# axxl_v0_1.net
KiCad netlist of a schematic drawn in EAGLE
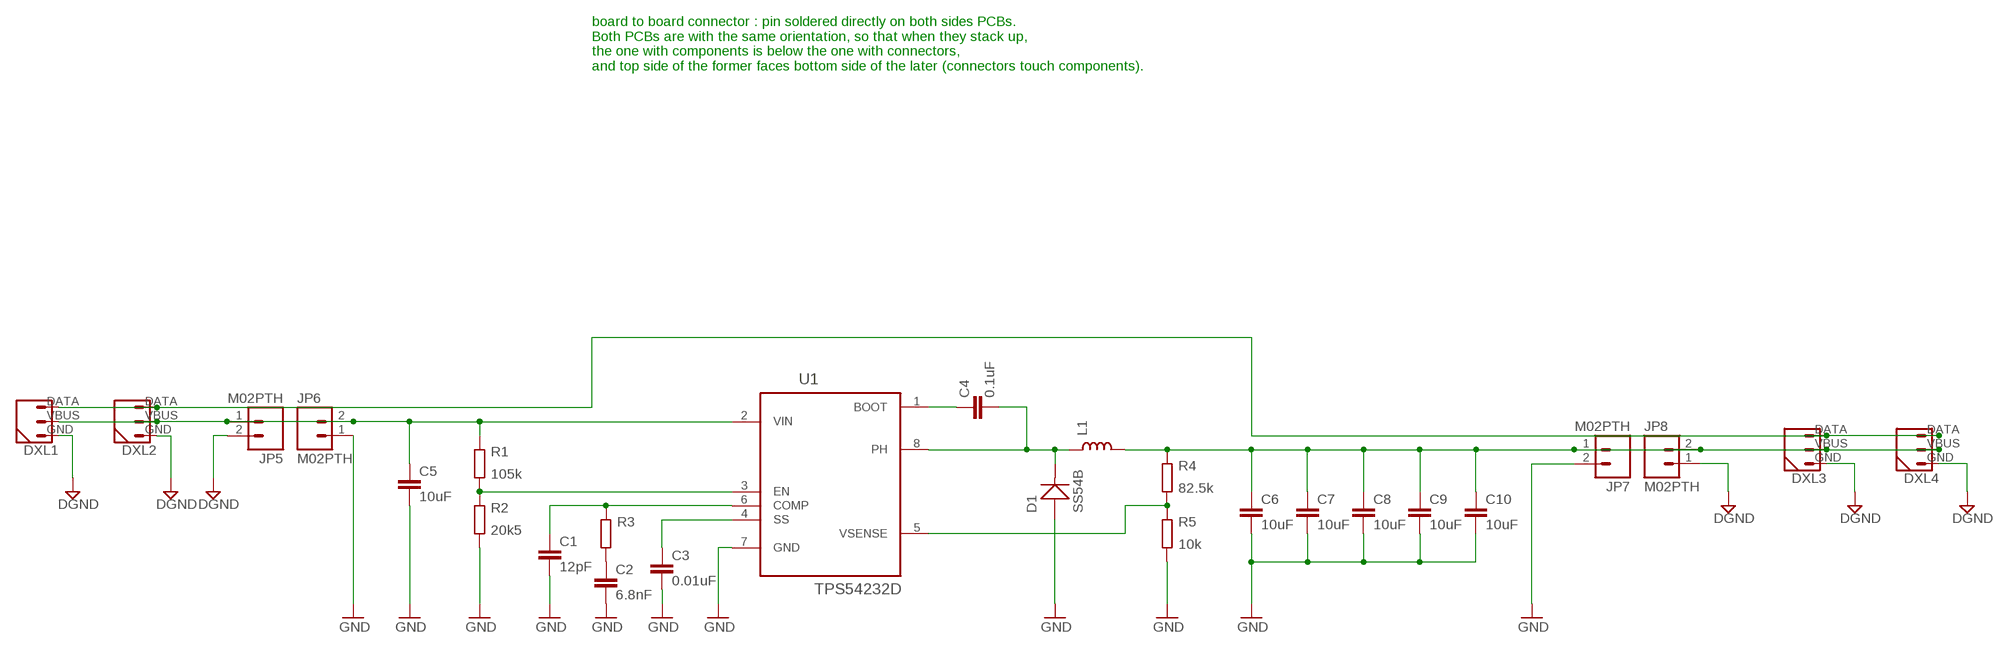
[diagram p0: schematic, sheet 1]

(export (version "E")
  (design (tool "Eeschema 10.0.6"))
  (components
    (comp (ref "C1")
      (value "12pF")
      (footprint "eagle-import:0402_N")
      (libsource (lib "eagle-import") (part "C0402"))
    )
    (comp (ref "C2")
      (value "6.8nF")
      (footprint "eagle-import:0402_N")
      (libsource (lib "eagle-import") (part "C0402"))
    )
    (comp (ref "C3")
      (value "0.01uF")
      (footprint "eagle-import:0402_N")
      (libsource (lib "eagle-import") (part "C0402"))
    )
    (comp (ref "C4")
      (value "0.1uF")
      (footprint "eagle-import:0402_N")
      (libsource (lib "eagle-import") (part "C0402"))
    )
    (comp (ref "C5")
      (value "10uF")
      (footprint "eagle-import:0805_N")
      (libsource (lib "eagle-import") (part "C0805"))
    )
    (comp (ref "C6")
      (value "10uF")
      (footprint "eagle-import:0805_N")
      (libsource (lib "eagle-import") (part "C0805"))
    )
    (comp (ref "C7")
      (value "10uF")
      (footprint "eagle-import:0805_N")
      (libsource (lib "eagle-import") (part "C0805"))
    )
    (comp (ref "C8")
      (value "10uF")
      (footprint "eagle-import:0805_N")
      (libsource (lib "eagle-import") (part "C0805"))
    )
    (comp (ref "C9")
      (value "10uF")
      (footprint "eagle-import:0805_N")
      (libsource (lib "eagle-import") (part "C0805"))
    )
    (comp (ref "C10")
      (value "10uF")
      (footprint "eagle-import:0805_N")
      (libsource (lib "eagle-import") (part "C0805"))
    )
    (comp (ref "D1")
      (value "SS54B")
      (footprint "eagle-import:SMB")
      (libsource (lib "eagle-import") (part "D-SMB"))
    )
    (comp (ref "DXL1")
      (value "DYNAMIXEL_3POS-R")
      (footprint "eagle-import:DYNAMIXEL_3POS_RIGHT")
      (libsource (lib "eagle-import") (part "DYNAMIXEL_3POS-R"))
    )
    (comp (ref "DXL2")
      (value "DYNAMIXEL_3POS-R")
      (footprint "eagle-import:DYNAMIXEL_3POS_RIGHT")
      (libsource (lib "eagle-import") (part "DYNAMIXEL_3POS-R"))
    )
    (comp (ref "DXL3")
      (value "DYNAMIXEL_3POS-XL-R")
      (footprint "eagle-import:DYNAMIXEL_XL_RIGHT")
      (libsource (lib "eagle-import") (part "DYNAMIXEL_3POS-XL-R"))
    )
    (comp (ref "DXL4")
      (value "DYNAMIXEL_3POS-XL-R")
      (footprint "eagle-import:DYNAMIXEL_XL_RIGHT")
      (libsource (lib "eagle-import") (part "DYNAMIXEL_3POS-XL-R"))
    )
    (comp (ref "JP5")
      (value "M02PTH")
      (footprint "eagle-import:1X02")
      (libsource (lib "eagle-import") (part "M02PTH"))
    )
    (comp (ref "JP6")
      (value "M02PTH")
      (footprint "eagle-import:1X02")
      (libsource (lib "eagle-import") (part "M02PTH"))
    )
    (comp (ref "JP7")
      (value "M02PTH")
      (footprint "eagle-import:1X02")
      (libsource (lib "eagle-import") (part "M02PTH"))
    )
    (comp (ref "JP8")
      (value "M02PTH")
      (footprint "eagle-import:1X02")
      (libsource (lib "eagle-import") (part "M02PTH"))
    )
    (comp (ref "L1")
      (value "L-SMD_8X8")
      (footprint "eagle-import:L_SRU8043")
      (libsource (lib "eagle-import") (part "L-SMD_8X8"))
    )
    (comp (ref "R1")
      (value "105k")
      (footprint "eagle-import:0402_N")
      (libsource (lib "eagle-import") (part "R0402"))
    )
    (comp (ref "R2")
      (value "20k5")
      (footprint "eagle-import:0402_N")
      (libsource (lib "eagle-import") (part "R0402"))
    )
    (comp (ref "R3")
      (value "R0402")
      (footprint "eagle-import:0402_N")
      (libsource (lib "eagle-import") (part "R0402"))
    )
    (comp (ref "R4")
      (value "82.5k")
      (footprint "eagle-import:0402_N")
      (libsource (lib "eagle-import") (part "R0402"))
    )
    (comp (ref "R5")
      (value "10k")
      (footprint "eagle-import:0402_N")
      (libsource (lib "eagle-import") (part "R0402"))
    )
    (comp (ref "U1")
      (value "TPS54232D")
      (footprint "eagle-import:SOIC127P600X175-8N")
      (libsource (lib "eagle-import") (part "TPS54232D"))
    )
  )
  (nets
    (net (code "1") (name "DGND") (class "Default")
      (node (ref "DXL1") (pin "GND") (pinfunction "1_GND") (pintype "bidirectional"))
      (node (ref "DXL2") (pin "GND") (pinfunction "1_GND") (pintype "bidirectional"))
      (node (ref "DXL3") (pin "GND") (pinfunction "1_GND") (pintype "bidirectional"))
      (node (ref "DXL4") (pin "GND") (pinfunction "1_GND") (pintype "bidirectional"))
      (node (ref "JP5") (pin "2") (pinfunction "2_2") (pintype "passive"))
      (node (ref "JP8") (pin "1") (pinfunction "1_1") (pintype "passive"))
    )
    (net (code "2") (name "GND") (class "Default")
      (node (ref "C1") (pin "2") (pinfunction "2_2") (pintype "passive"))
      (node (ref "C10") (pin "2") (pinfunction "2_2") (pintype "passive"))
      (node (ref "C2") (pin "2") (pinfunction "2_2") (pintype "passive"))
      (node (ref "C3") (pin "2") (pinfunction "2_2") (pintype "passive"))
      (node (ref "C5") (pin "2") (pinfunction "2_2") (pintype "passive"))
      (node (ref "C6") (pin "2") (pinfunction "2_2") (pintype "passive"))
      (node (ref "C7") (pin "2") (pinfunction "2_2") (pintype "passive"))
      (node (ref "C8") (pin "2") (pinfunction "2_2") (pintype "passive"))
      (node (ref "C9") (pin "2") (pinfunction "2_2") (pintype "passive"))
      (node (ref "D1") (pin "+") (pinfunction "+_+") (pintype "passive"))
      (node (ref "JP6") (pin "1") (pinfunction "1_1") (pintype "passive"))
      (node (ref "JP7") (pin "2") (pinfunction "2_2") (pintype "passive"))
      (node (ref "R2") (pin "1") (pinfunction "1_1") (pintype "passive"))
      (node (ref "R5") (pin "1") (pinfunction "1_1") (pintype "passive"))
      (node (ref "U1") (pin "7") (pinfunction "GND_7") (pintype "passive"))
    )
    (net (code "3") (name "Net-(C2-Pad1)") (class "Default")
      (node (ref "C2") (pin "1") (pinfunction "1_1") (pintype "passive"))
      (node (ref "R3") (pin "1") (pinfunction "1_1") (pintype "passive"))
    )
    (net (code "4") (name "Net-(DXL1-2)") (class "Default")
      (node (ref "C5") (pin "1") (pinfunction "1_1") (pintype "passive"))
      (node (ref "DXL1") (pin "VBUS") (pinfunction "2_VBUS") (pintype "bidirectional"))
      (node (ref "DXL2") (pin "VBUS") (pinfunction "2_VBUS") (pintype "bidirectional"))
      (node (ref "JP5") (pin "1") (pinfunction "1_1") (pintype "passive"))
      (node (ref "JP6") (pin "2") (pinfunction "2_2") (pintype "passive"))
      (node (ref "R1") (pin "2") (pinfunction "2_2") (pintype "passive"))
      (node (ref "U1") (pin "2") (pinfunction "VIN_2") (pintype "power_in"))
    )
    (net (code "5") (name "Net-(DXL1-3)") (class "Default")
      (node (ref "DXL1") (pin "DATA") (pinfunction "3_DATA") (pintype "bidirectional"))
      (node (ref "DXL2") (pin "DATA") (pinfunction "3_DATA") (pintype "bidirectional"))
      (node (ref "DXL3") (pin "DATA") (pinfunction "3_DATA") (pintype "bidirectional"))
      (node (ref "DXL4") (pin "DATA") (pinfunction "3_DATA") (pintype "bidirectional"))
    )
    (net (code "6") (name "Net-(DXL3-2)") (class "Default")
      (node (ref "C10") (pin "1") (pinfunction "1_1") (pintype "passive"))
      (node (ref "C6") (pin "1") (pinfunction "1_1") (pintype "passive"))
      (node (ref "C7") (pin "1") (pinfunction "1_1") (pintype "passive"))
      (node (ref "C8") (pin "1") (pinfunction "1_1") (pintype "passive"))
      (node (ref "C9") (pin "1") (pinfunction "1_1") (pintype "passive"))
      (node (ref "DXL3") (pin "VBUS") (pinfunction "2_VBUS") (pintype "bidirectional"))
      (node (ref "DXL4") (pin "VBUS") (pinfunction "2_VBUS") (pintype "bidirectional"))
      (node (ref "JP7") (pin "1") (pinfunction "1_1") (pintype "passive"))
      (node (ref "JP8") (pin "2") (pinfunction "2_2") (pintype "passive"))
      (node (ref "L1") (pin "P$2") (pinfunction "2_P$2") (pintype "passive"))
      (node (ref "R4") (pin "2") (pinfunction "2_2") (pintype "passive"))
    )
    (net (code "7") (name "Net-(L1-1)") (class "Default")
      (node (ref "C4") (pin "2") (pinfunction "2_2") (pintype "passive"))
      (node (ref "D1") (pin "-") (pinfunction "-_-") (pintype "passive"))
      (node (ref "L1") (pin "P$1") (pinfunction "1_P$1") (pintype "passive"))
      (node (ref "U1") (pin "8") (pinfunction "PH_8") (pintype "input"))
    )
    (net (code "8") (name "Net-(U1-BOOT)") (class "Default")
      (node (ref "C4") (pin "1") (pinfunction "1_1") (pintype "passive"))
      (node (ref "U1") (pin "1") (pinfunction "BOOT_1") (pintype "input"))
    )
    (net (code "9") (name "Net-(U1-COMP)") (class "Default")
      (node (ref "C1") (pin "1") (pinfunction "1_1") (pintype "passive"))
      (node (ref "R3") (pin "2") (pinfunction "2_2") (pintype "passive"))
      (node (ref "U1") (pin "6") (pinfunction "COMP_6") (pintype "output"))
    )
    (net (code "10") (name "Net-(U1-EN)") (class "Default")
      (node (ref "R1") (pin "1") (pinfunction "1_1") (pintype "passive"))
      (node (ref "R2") (pin "2") (pinfunction "2_2") (pintype "passive"))
      (node (ref "U1") (pin "3") (pinfunction "EN_3") (pintype "input"))
    )
    (net (code "11") (name "Net-(U1-SS)") (class "Default")
      (node (ref "C3") (pin "1") (pinfunction "1_1") (pintype "passive"))
      (node (ref "U1") (pin "4") (pinfunction "SS_4") (pintype "input"))
    )
    (net (code "12") (name "Net-(U1-VSENSE)") (class "Default")
      (node (ref "R4") (pin "1") (pinfunction "1_1") (pintype "passive"))
      (node (ref "R5") (pin "2") (pinfunction "2_2") (pintype "passive"))
      (node (ref "U1") (pin "5") (pinfunction "VSENSE_5") (pintype "input"))
    )
  )
)
